# DC_Motor_driver.net
KiCad netlist of a schematic drawn in EAGLE
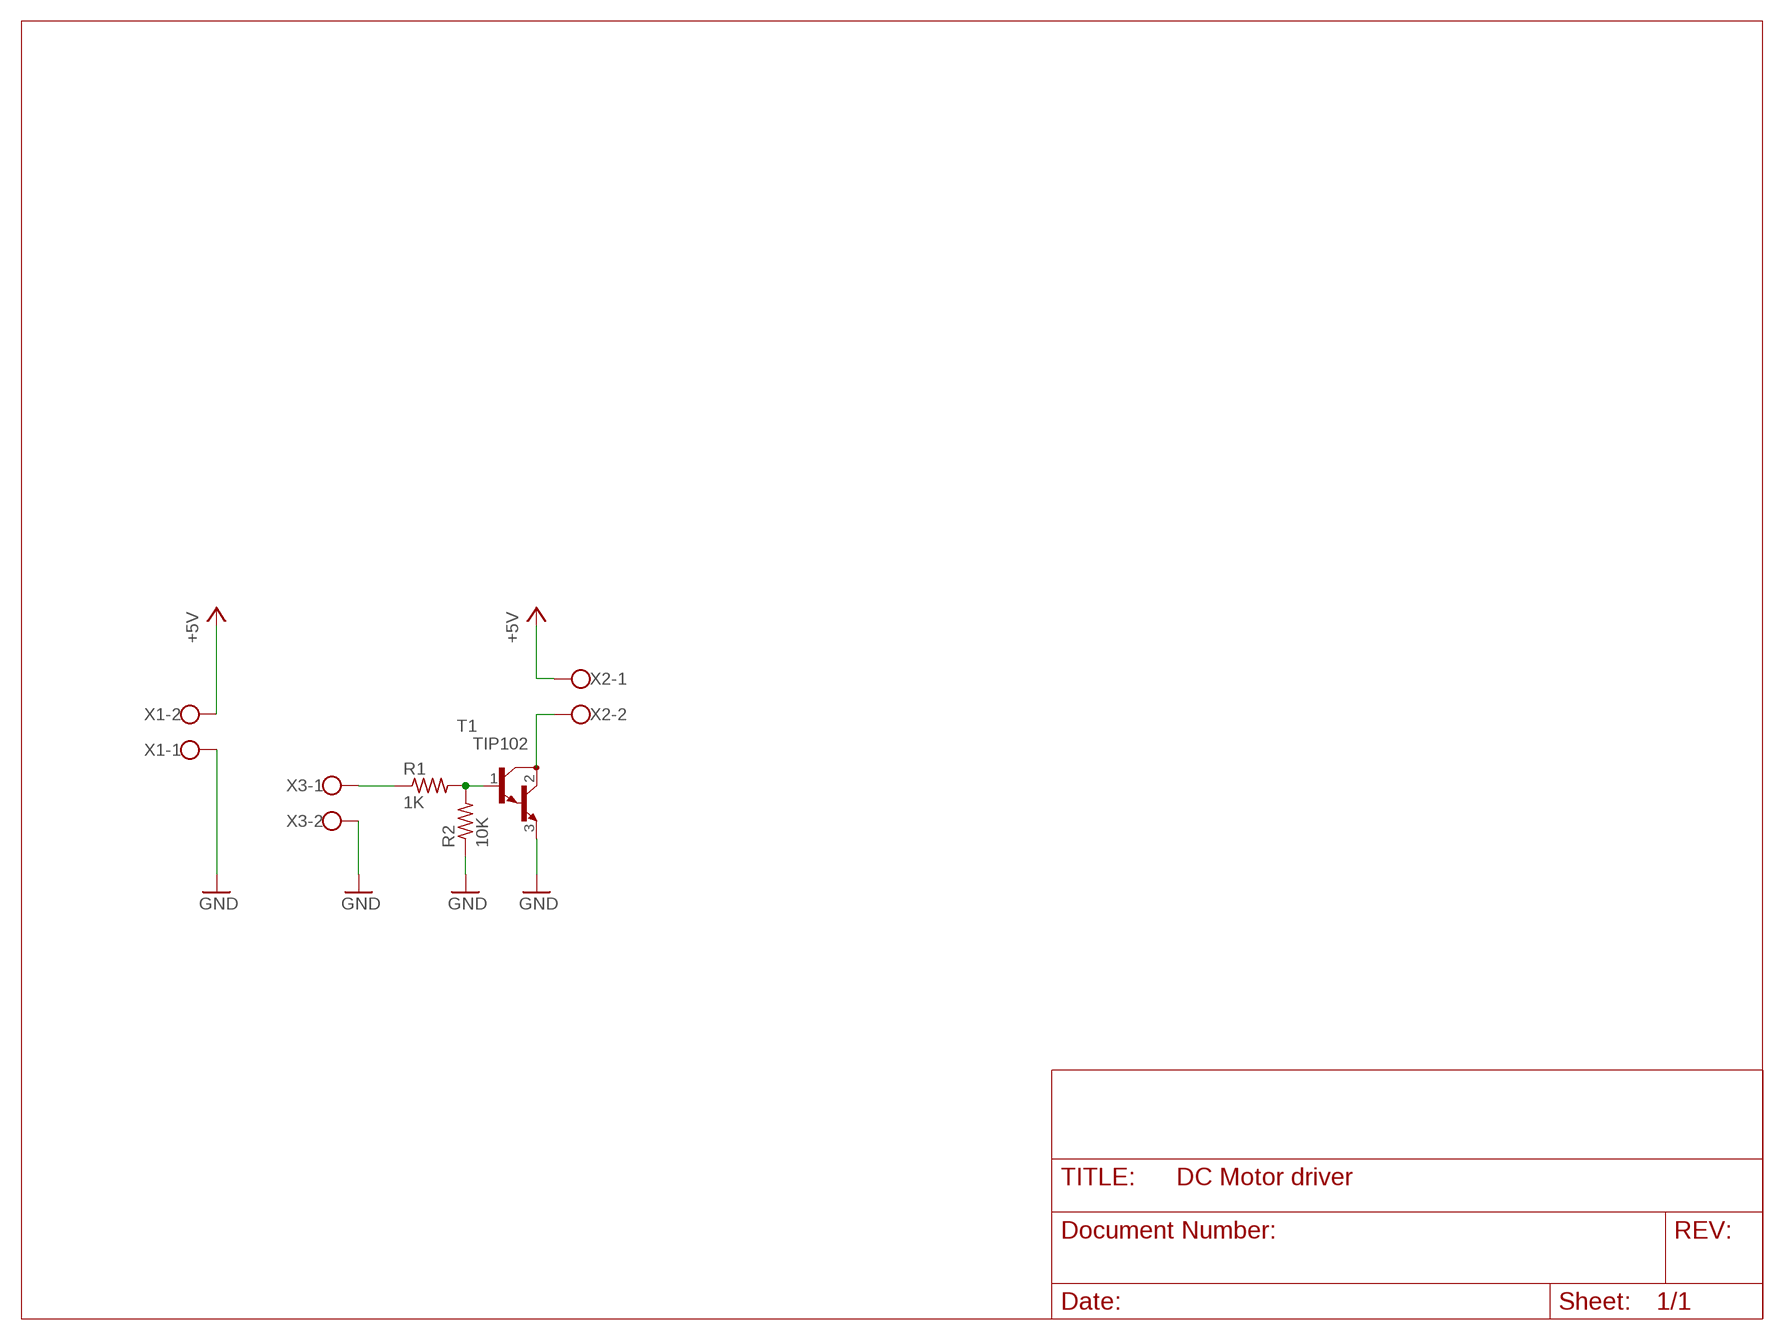
[diagram p0: schematic, sheet 1]

(export (version "E")
  (design (tool "Eeschema 10.0.6"))
  (components
    (comp (ref "R1")
      (value "1K")
      (footprint "eagle-import:0309_12")
      (libsource (lib "eagle-import") (part "R-US_0309/12"))
    )
    (comp (ref "R2")
      (value "10K")
      (footprint "eagle-import:0309_12")
      (libsource (lib "eagle-import") (part "R-US_0309/12"))
    )
    (comp (ref "T1")
      (value "TIP102")
      (footprint "eagle-import:TO220")
      (libsource (lib "eagle-import") (part "TIP122"))
    )
    (comp (ref "X1")
      (value "W237-102")
      (footprint "eagle-import:W237-102")
      (fields (field (name "MPN") "237-102"))
      (libsource (lib "eagle-import") (part "W237-102"))
    )
    (comp (ref "X2")
      (value "W237-102")
      (footprint "eagle-import:W237-102")
      (fields (field (name "MPN") "237-102"))
      (libsource (lib "eagle-import") (part "W237-102"))
    )
    (comp (ref "X3")
      (value "W237-102")
      (footprint "eagle-import:W237-102")
      (fields (field (name "MPN") "237-102"))
      (libsource (lib "eagle-import") (part "W237-102"))
    )
  )
  (nets
    (net (code "1") (name "+5V") (class "Default")
      (node (ref "X1") (pin "2") (pinfunction "KL_2") (pintype "passive"))
      (node (ref "X2") (pin "1") (pinfunction "KL_1") (pintype "passive"))
    )
    (net (code "2") (name "GND") (class "Default")
      (node (ref "R2") (pin "1") (pinfunction "1_1") (pintype "passive"))
      (node (ref "T1") (pin "3") (pinfunction "E_3") (pintype "passive"))
      (node (ref "X1") (pin "1") (pinfunction "KL_1") (pintype "passive"))
      (node (ref "X3") (pin "2") (pinfunction "KL_2") (pintype "passive"))
    )
    (net (code "3") (name "Net-(T1-B)") (class "Default")
      (node (ref "R1") (pin "2") (pinfunction "2_2") (pintype "passive"))
      (node (ref "R2") (pin "2") (pinfunction "2_2") (pintype "passive"))
      (node (ref "T1") (pin "1") (pinfunction "B_1") (pintype "passive"))
    )
    (net (code "4") (name "Net-(T1-C)") (class "Default")
      (node (ref "T1") (pin "2") (pinfunction "C_2") (pintype "passive"))
      (node (ref "X2") (pin "2") (pinfunction "KL_2") (pintype "passive"))
    )
    (net (code "5") (name "Net-(X3A-KL)") (class "Default")
      (node (ref "R1") (pin "1") (pinfunction "1_1") (pintype "passive"))
      (node (ref "X3") (pin "1") (pinfunction "KL_1") (pintype "passive"))
    )
  )
)
